# EPS_Stack_Header.net
KiCad netlist of a schematic drawn in Altium Designer
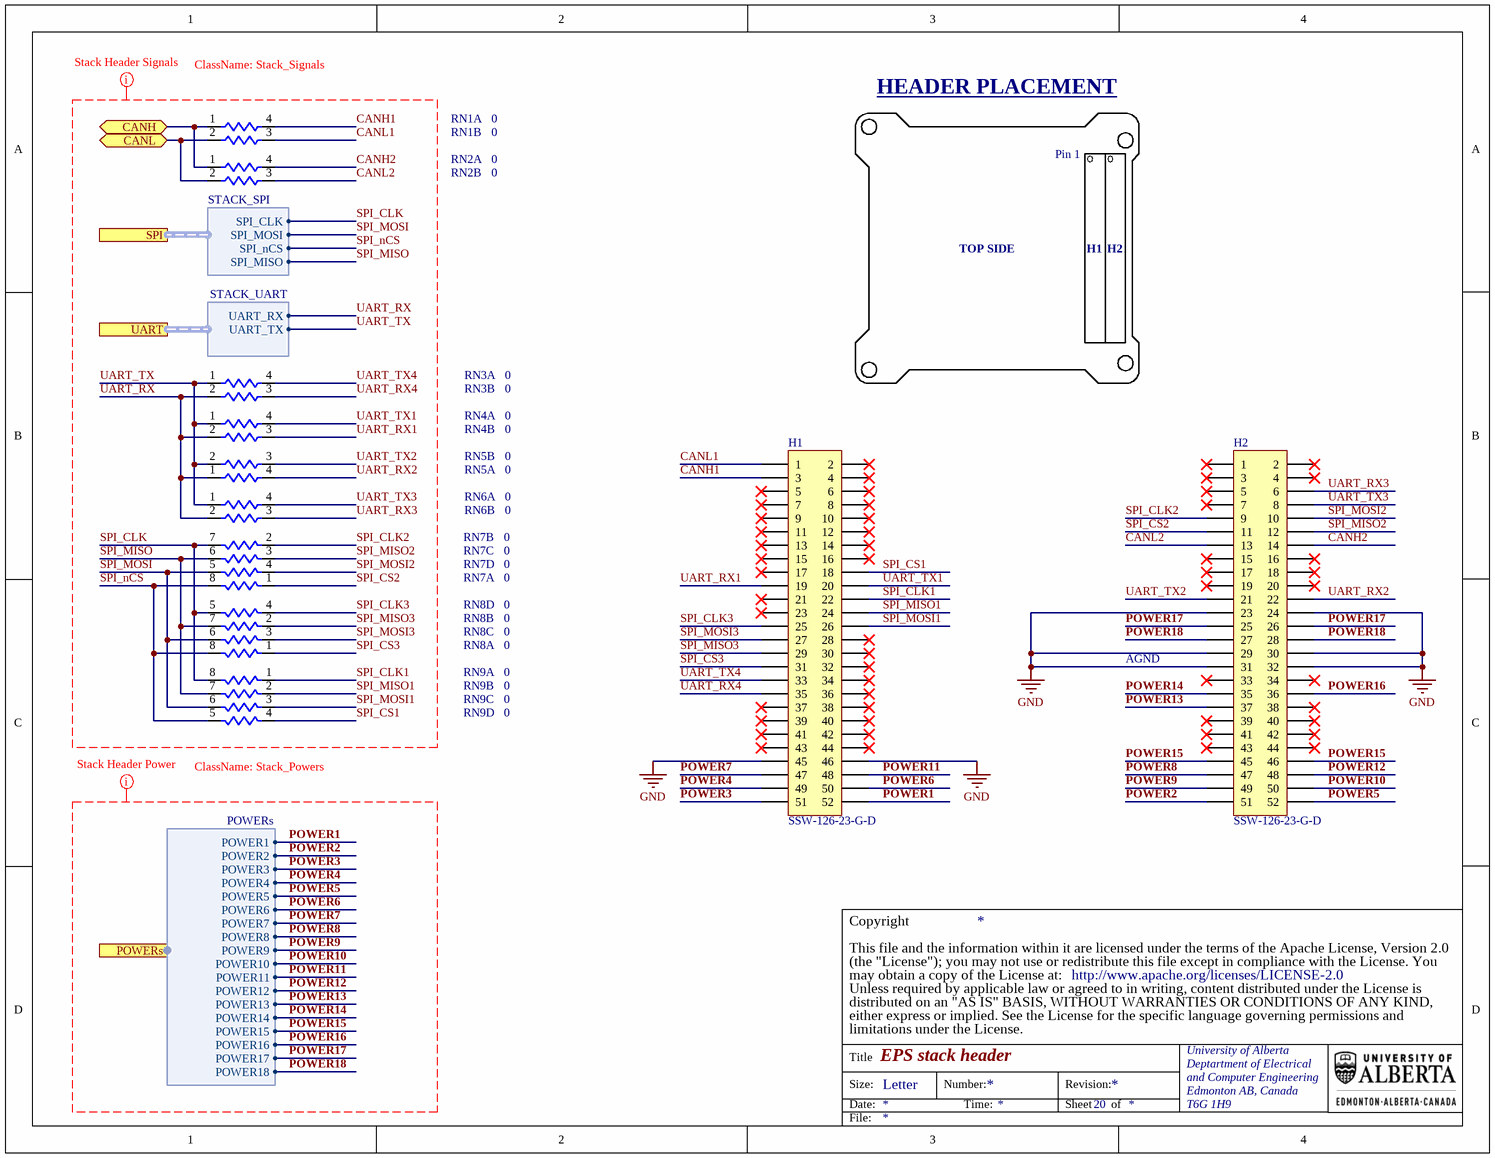
[diagram p0: EPS Stack Header.SchDoc]

(export (version "E")
  (design (tool "Eeschema 10.0.6"))
  (components
    (comp (ref "H1")
      (value "SSW-126-23-G-D")
      (footprint "SSW-126-23-G-D")
      (fields (field (name "PART NUMBER") "PP-SAM-00002") (field (name "PUBLISHER") "AlbertaSat"))
      (libsource (lib "Database") (part "Header 26X2"))
    )
    (comp (ref "H2")
      (value "SSW-126-23-G-D")
      (footprint "SSW-126-23-G-D")
      (fields (field (name "PART NUMBER") "PP-SAM-00002") (field (name "PUBLISHER") "AlbertaSat"))
      (libsource (lib "Database") (part "Header 26X2"))
    )
    (comp (ref "RN1")
      (value "0")
      (footprint "PANA-EXB24V")
      (description "RES ARRAY 2 RES ZERO OHM 0404")
      (fields (field (name "PART NUMBER") "20039") (field (name "MANUFACTURER PART NUMBER") "EXB-24VR000X"))
      (libsource (lib "Database") (part "Res2 Pack1"))
    )
    (comp (ref "RN2")
      (value "0")
      (footprint "PANA-EXB24V")
      (description "RES ARRAY 2 RES ZERO OHM 0404")
      (fields (field (name "PART NUMBER") "20039") (field (name "MANUFACTURER PART NUMBER") "EXB-24VR000X"))
      (libsource (lib "Database") (part "Res2 Pack1"))
    )
    (comp (ref "RN3")
      (value "0")
      (footprint "PANA-EXB24V")
      (description "RES ARRAY 2 RES ZERO OHM 0404")
      (fields (field (name "PART NUMBER") "20039") (field (name "MANUFACTURER PART NUMBER") "EXB-24VR000X"))
      (libsource (lib "Database") (part "Res2 Pack1"))
    )
    (comp (ref "RN4")
      (value "0")
      (footprint "PANA-EXB24V")
      (description "RES ARRAY 2 RES ZERO OHM 0404")
      (fields (field (name "PART NUMBER") "20039") (field (name "MANUFACTURER PART NUMBER") "EXB-24VR000X"))
      (libsource (lib "Database") (part "Res2 Pack1"))
    )
    (comp (ref "RN5")
      (value "0")
      (footprint "PANA-EXB24V")
      (description "RES ARRAY 2 RES ZERO OHM 0404")
      (fields (field (name "PART NUMBER") "20039") (field (name "MANUFACTURER PART NUMBER") "EXB-24VR000X"))
      (libsource (lib "Database") (part "Res2 Pack1"))
    )
    (comp (ref "RN6")
      (value "0")
      (footprint "PANA-EXB24V")
      (description "RES ARRAY 2 RES ZERO OHM 0404")
      (fields (field (name "PART NUMBER") "20039") (field (name "MANUFACTURER PART NUMBER") "EXB-24VR000X"))
      (libsource (lib "Database") (part "Res2 Pack1"))
    )
    (comp (ref "RN7")
      (value "0")
      (footprint "PANA-EXB28V")
      (description "RES ARRAY 4 RES ZERO OHM 0804")
      (fields (field (name "PART NUMBER") "19874") (field (name "MANUFACTURER PART NUMBER") "EXB-28VR000X"))
      (libsource (lib "Database") (part "Res4 Pack1"))
    )
    (comp (ref "RN8")
      (value "0")
      (footprint "PANA-EXB28V")
      (description "RES ARRAY 4 RES ZERO OHM 0804")
      (fields (field (name "PART NUMBER") "19874") (field (name "MANUFACTURER PART NUMBER") "EXB-28VR000X"))
      (libsource (lib "Database") (part "Res4 Pack1"))
    )
    (comp (ref "RN9")
      (value "0")
      (footprint "PANA-EXB28V")
      (description "RES ARRAY 4 RES ZERO OHM 0804")
      (fields (field (name "PART NUMBER") "19874") (field (name "MANUFACTURER PART NUMBER") "EXB-28VR000X"))
      (libsource (lib "Database") (part "Res4 Pack1"))
    )
  )
  (nets
    (net (code "4") (name "/CANH") (class "Default")
      (node (ref "RN1") (pin "1") (pinfunction "1_1") (pintype "passive"))
      (node (ref "RN2") (pin "1") (pinfunction "1_1") (pintype "passive"))
    )
    (net (code "5") (name "/CANH1") (class "Default")
      (node (ref "H1") (pin "3") (pinfunction "3_3") (pintype "passive"))
      (node (ref "RN1") (pin "4") (pinfunction "4_4") (pintype "passive"))
    )
    (net (code "6") (name "/CANH2") (class "Default")
      (node (ref "H2") (pin "14") (pinfunction "14_14") (pintype "passive"))
      (node (ref "RN2") (pin "4") (pinfunction "4_4") (pintype "passive"))
    )
    (net (code "7") (name "/CANL") (class "Default")
      (node (ref "RN1") (pin "2") (pinfunction "2_2") (pintype "passive"))
      (node (ref "RN2") (pin "2") (pinfunction "2_2") (pintype "passive"))
    )
    (net (code "8") (name "/CANL1") (class "Default")
      (node (ref "H1") (pin "1") (pinfunction "1_1") (pintype "passive"))
      (node (ref "RN1") (pin "3") (pinfunction "3_3") (pintype "passive"))
    )
    (net (code "9") (name "/CANL2") (class "Default")
      (node (ref "H2") (pin "13") (pinfunction "13_13") (pintype "passive"))
      (node (ref "RN2") (pin "3") (pinfunction "3_3") (pintype "passive"))
    )
    (net (code "10") (name "/POWER1") (class "Default")
      (node (ref "H1") (pin "52") (pinfunction "52_52") (pintype "passive"))
    )
    (net (code "11") (name "/POWER2") (class "Default")
      (node (ref "H2") (pin "51") (pinfunction "51_51") (pintype "passive"))
    )
    (net (code "12") (name "/POWER3") (class "Default")
      (node (ref "H1") (pin "51") (pinfunction "51_51") (pintype "passive"))
    )
    (net (code "13") (name "/POWER4") (class "Default")
      (node (ref "H1") (pin "49") (pinfunction "49_49") (pintype "passive"))
    )
    (net (code "14") (name "/POWER5") (class "Default")
      (node (ref "H2") (pin "52") (pinfunction "52_52") (pintype "passive"))
    )
    (net (code "15") (name "/POWER6") (class "Default")
      (node (ref "H1") (pin "50") (pinfunction "50_50") (pintype "passive"))
    )
    (net (code "16") (name "/POWER7") (class "Default")
      (node (ref "H1") (pin "47") (pinfunction "47_47") (pintype "passive"))
    )
    (net (code "17") (name "/POWER8") (class "Default")
      (node (ref "H2") (pin "47") (pinfunction "47_47") (pintype "passive"))
    )
    (net (code "18") (name "/POWER9") (class "Default")
      (node (ref "H2") (pin "49") (pinfunction "49_49") (pintype "passive"))
    )
    (net (code "19") (name "/POWER10") (class "Default")
      (node (ref "H2") (pin "50") (pinfunction "50_50") (pintype "passive"))
    )
    (net (code "20") (name "/POWER11") (class "Default")
      (node (ref "H1") (pin "48") (pinfunction "48_48") (pintype "passive"))
    )
    (net (code "21") (name "/POWER12") (class "Default")
      (node (ref "H2") (pin "48") (pinfunction "48_48") (pintype "passive"))
    )
    (net (code "22") (name "/POWER13") (class "Default")
      (node (ref "H2") (pin "37") (pinfunction "37_37") (pintype "passive"))
    )
    (net (code "23") (name "/POWER14") (class "Default")
      (node (ref "H2") (pin "35") (pinfunction "35_35") (pintype "passive"))
    )
    (net (code "24") (name "/POWER15") (class "Default")
      (node (ref "H2") (pin "45") (pinfunction "45_45") (pintype "passive"))
      (node (ref "H2") (pin "46") (pinfunction "46_46") (pintype "passive"))
    )
    (net (code "25") (name "/POWER16") (class "Default")
      (node (ref "H2") (pin "36") (pinfunction "36_36") (pintype "passive"))
    )
    (net (code "26") (name "/POWER17") (class "Default")
      (node (ref "H2") (pin "25") (pinfunction "25_25") (pintype "passive"))
      (node (ref "H2") (pin "26") (pinfunction "26_26") (pintype "passive"))
    )
    (net (code "27") (name "/POWER18") (class "Default")
      (node (ref "H2") (pin "27") (pinfunction "27_27") (pintype "passive"))
      (node (ref "H2") (pin "28") (pinfunction "28_28") (pintype "passive"))
    )
    (net (code "28") (name "/SPI_CLK") (class "Default")
      (node (ref "RN7") (pin "7") (pinfunction "7_7") (pintype "passive"))
      (node (ref "RN8") (pin "5") (pinfunction "5_5") (pintype "passive"))
      (node (ref "RN9") (pin "8") (pinfunction "8_8") (pintype "passive"))
    )
    (net (code "29") (name "/SPI_CLK1") (class "Default")
      (node (ref "H1") (pin "22") (pinfunction "22_22") (pintype "passive"))
      (node (ref "RN9") (pin "1") (pinfunction "1_1") (pintype "passive"))
    )
    (net (code "30") (name "/SPI_CLK2") (class "Default")
      (node (ref "H2") (pin "9") (pinfunction "9_9") (pintype "passive"))
      (node (ref "RN7") (pin "2") (pinfunction "2_2") (pintype "passive"))
    )
    (net (code "31") (name "/SPI_CLK3") (class "Default")
      (node (ref "H1") (pin "25") (pinfunction "25_25") (pintype "passive"))
      (node (ref "RN8") (pin "4") (pinfunction "4_4") (pintype "passive"))
    )
    (net (code "32") (name "/SPI_CS1") (class "Default")
      (node (ref "H1") (pin "18") (pinfunction "18_18") (pintype "passive"))
      (node (ref "RN9") (pin "4") (pinfunction "4_4") (pintype "passive"))
    )
    (net (code "33") (name "/SPI_CS2") (class "Default")
      (node (ref "H2") (pin "11") (pinfunction "11_11") (pintype "passive"))
      (node (ref "RN7") (pin "1") (pinfunction "1_1") (pintype "passive"))
    )
    (net (code "34") (name "/SPI_CS3") (class "Default")
      (node (ref "H1") (pin "31") (pinfunction "31_31") (pintype "passive"))
      (node (ref "RN8") (pin "1") (pinfunction "1_1") (pintype "passive"))
    )
    (net (code "35") (name "/SPI_MISO") (class "Default")
      (node (ref "RN7") (pin "6") (pinfunction "6_6") (pintype "passive"))
      (node (ref "RN8") (pin "7") (pinfunction "7_7") (pintype "passive"))
      (node (ref "RN9") (pin "7") (pinfunction "7_7") (pintype "passive"))
    )
    (net (code "36") (name "/SPI_MISO1") (class "Default")
      (node (ref "H1") (pin "24") (pinfunction "24_24") (pintype "passive"))
      (node (ref "RN9") (pin "2") (pinfunction "2_2") (pintype "passive"))
    )
    (net (code "37") (name "/SPI_MISO2") (class "Default")
      (node (ref "H2") (pin "12") (pinfunction "12_12") (pintype "passive"))
      (node (ref "RN7") (pin "3") (pinfunction "3_3") (pintype "passive"))
    )
    (net (code "38") (name "/SPI_MISO3") (class "Default")
      (node (ref "H1") (pin "29") (pinfunction "29_29") (pintype "passive"))
      (node (ref "RN8") (pin "2") (pinfunction "2_2") (pintype "passive"))
    )
    (net (code "39") (name "/SPI_MOSI") (class "Default")
      (node (ref "RN7") (pin "5") (pinfunction "5_5") (pintype "passive"))
      (node (ref "RN8") (pin "6") (pinfunction "6_6") (pintype "passive"))
      (node (ref "RN9") (pin "6") (pinfunction "6_6") (pintype "passive"))
    )
    (net (code "40") (name "/SPI_MOSI1") (class "Default")
      (node (ref "H1") (pin "26") (pinfunction "26_26") (pintype "passive"))
      (node (ref "RN9") (pin "3") (pinfunction "3_3") (pintype "passive"))
    )
    (net (code "41") (name "/SPI_MOSI2") (class "Default")
      (node (ref "H2") (pin "10") (pinfunction "10_10") (pintype "passive"))
      (node (ref "RN7") (pin "4") (pinfunction "4_4") (pintype "passive"))
    )
    (net (code "42") (name "/SPI_MOSI3") (class "Default")
      (node (ref "H1") (pin "27") (pinfunction "27_27") (pintype "passive"))
      (node (ref "RN8") (pin "3") (pinfunction "3_3") (pintype "passive"))
    )
    (net (code "43") (name "/SPI_nCS") (class "Default")
      (node (ref "RN7") (pin "8") (pinfunction "8_8") (pintype "passive"))
      (node (ref "RN8") (pin "8") (pinfunction "8_8") (pintype "passive"))
      (node (ref "RN9") (pin "5") (pinfunction "5_5") (pintype "passive"))
    )
    (net (code "44") (name "/UART_RX") (class "Default")
      (node (ref "RN3") (pin "2") (pinfunction "2_2") (pintype "passive"))
      (node (ref "RN4") (pin "2") (pinfunction "2_2") (pintype "passive"))
      (node (ref "RN5") (pin "1") (pinfunction "1_1") (pintype "passive"))
      (node (ref "RN6") (pin "2") (pinfunction "2_2") (pintype "passive"))
    )
    (net (code "45") (name "/UART_RX1") (class "Default")
      (node (ref "H1") (pin "19") (pinfunction "19_19") (pintype "passive"))
      (node (ref "RN4") (pin "3") (pinfunction "3_3") (pintype "passive"))
    )
    (net (code "46") (name "/UART_RX2") (class "Default")
      (node (ref "H2") (pin "22") (pinfunction "22_22") (pintype "passive"))
      (node (ref "RN5") (pin "4") (pinfunction "4_4") (pintype "passive"))
    )
    (net (code "47") (name "/UART_RX3") (class "Default")
      (node (ref "H2") (pin "6") (pinfunction "6_6") (pintype "passive"))
      (node (ref "RN6") (pin "3") (pinfunction "3_3") (pintype "passive"))
    )
    (net (code "48") (name "/UART_RX4") (class "Default")
      (node (ref "H1") (pin "35") (pinfunction "35_35") (pintype "passive"))
      (node (ref "RN3") (pin "3") (pinfunction "3_3") (pintype "passive"))
    )
    (net (code "49") (name "/UART_TX") (class "Default")
      (node (ref "RN3") (pin "1") (pinfunction "1_1") (pintype "passive"))
      (node (ref "RN4") (pin "1") (pinfunction "1_1") (pintype "passive"))
      (node (ref "RN5") (pin "2") (pinfunction "2_2") (pintype "passive"))
      (node (ref "RN6") (pin "1") (pinfunction "1_1") (pintype "passive"))
    )
    (net (code "50") (name "/UART_TX1") (class "Default")
      (node (ref "H1") (pin "20") (pinfunction "20_20") (pintype "passive"))
      (node (ref "RN4") (pin "4") (pinfunction "4_4") (pintype "passive"))
    )
    (net (code "51") (name "/UART_TX2") (class "Default")
      (node (ref "H2") (pin "21") (pinfunction "21_21") (pintype "passive"))
      (node (ref "RN5") (pin "3") (pinfunction "3_3") (pintype "passive"))
    )
    (net (code "52") (name "/UART_TX3") (class "Default")
      (node (ref "H2") (pin "8") (pinfunction "8_8") (pintype "passive"))
      (node (ref "RN6") (pin "4") (pinfunction "4_4") (pintype "passive"))
    )
    (net (code "53") (name "/UART_TX4") (class "Default")
      (node (ref "H1") (pin "33") (pinfunction "33_33") (pintype "passive"))
      (node (ref "RN3") (pin "4") (pinfunction "4_4") (pintype "passive"))
    )
    (net (code "57") (name "GND") (class "Default")
      (node (ref "H1") (pin "45") (pinfunction "45_45") (pintype "passive"))
      (node (ref "H1") (pin "46") (pinfunction "46_46") (pintype "passive"))
      (node (ref "H2") (pin "23") (pinfunction "23_23") (pintype "passive"))
      (node (ref "H2") (pin "24") (pinfunction "24_24") (pintype "passive"))
      (node (ref "H2") (pin "29") (pinfunction "29_29") (pintype "passive"))
      (node (ref "H2") (pin "30") (pinfunction "30_30") (pintype "passive"))
      (node (ref "H2") (pin "31") (pinfunction "31_31") (pintype "passive"))
      (node (ref "H2") (pin "32") (pinfunction "32_32") (pintype "passive"))
    )
    (net (code "58") (name "unconnected-(H1-Pad2)") (class "Default")
      (node (ref "H1") (pin "2") (pinfunction "2_2") (pintype "passive+no_connect"))
    )
    (net (code "59") (name "unconnected-(H1-Pad4)") (class "Default")
      (node (ref "H1") (pin "4") (pinfunction "4_4") (pintype "passive+no_connect"))
    )
    (net (code "60") (name "unconnected-(H1-Pad5)") (class "Default")
      (node (ref "H1") (pin "5") (pinfunction "5_5") (pintype "passive+no_connect"))
    )
    (net (code "61") (name "unconnected-(H1-Pad6)") (class "Default")
      (node (ref "H1") (pin "6") (pinfunction "6_6") (pintype "passive+no_connect"))
    )
    (net (code "62") (name "unconnected-(H1-Pad7)") (class "Default")
      (node (ref "H1") (pin "7") (pinfunction "7_7") (pintype "passive+no_connect"))
    )
    (net (code "63") (name "unconnected-(H1-Pad8)") (class "Default")
      (node (ref "H1") (pin "8") (pinfunction "8_8") (pintype "passive+no_connect"))
    )
    (net (code "64") (name "unconnected-(H1-Pad9)") (class "Default")
      (node (ref "H1") (pin "9") (pinfunction "9_9") (pintype "passive+no_connect"))
    )
    (net (code "65") (name "unconnected-(H1-Pad10)") (class "Default")
      (node (ref "H1") (pin "10") (pinfunction "10_10") (pintype "passive+no_connect"))
    )
    (net (code "66") (name "unconnected-(H1-Pad11)") (class "Default")
      (node (ref "H1") (pin "11") (pinfunction "11_11") (pintype "passive+no_connect"))
    )
    (net (code "67") (name "unconnected-(H1-Pad12)") (class "Default")
      (node (ref "H1") (pin "12") (pinfunction "12_12") (pintype "passive+no_connect"))
    )
    (net (code "68") (name "unconnected-(H1-Pad13)") (class "Default")
      (node (ref "H1") (pin "13") (pinfunction "13_13") (pintype "passive+no_connect"))
    )
    (net (code "69") (name "unconnected-(H1-Pad14)") (class "Default")
      (node (ref "H1") (pin "14") (pinfunction "14_14") (pintype "passive+no_connect"))
    )
    (net (code "70") (name "unconnected-(H1-Pad15)") (class "Default")
      (node (ref "H1") (pin "15") (pinfunction "15_15") (pintype "passive+no_connect"))
    )
    (net (code "71") (name "unconnected-(H1-Pad16)") (class "Default")
      (node (ref "H1") (pin "16") (pinfunction "16_16") (pintype "passive+no_connect"))
    )
    (net (code "72") (name "unconnected-(H1-Pad17)") (class "Default")
      (node (ref "H1") (pin "17") (pinfunction "17_17") (pintype "passive+no_connect"))
    )
    (net (code "73") (name "unconnected-(H1-Pad21)") (class "Default")
      (node (ref "H1") (pin "21") (pinfunction "21_21") (pintype "passive+no_connect"))
    )
    (net (code "74") (name "unconnected-(H1-Pad23)") (class "Default")
      (node (ref "H1") (pin "23") (pinfunction "23_23") (pintype "passive+no_connect"))
    )
    (net (code "75") (name "unconnected-(H1-Pad28)") (class "Default")
      (node (ref "H1") (pin "28") (pinfunction "28_28") (pintype "passive+no_connect"))
    )
    (net (code "76") (name "unconnected-(H1-Pad30)") (class "Default")
      (node (ref "H1") (pin "30") (pinfunction "30_30") (pintype "passive+no_connect"))
    )
    (net (code "77") (name "unconnected-(H1-Pad32)") (class "Default")
      (node (ref "H1") (pin "32") (pinfunction "32_32") (pintype "passive+no_connect"))
    )
    (net (code "78") (name "unconnected-(H1-Pad34)") (class "Default")
      (node (ref "H1") (pin "34") (pinfunction "34_34") (pintype "passive+no_connect"))
    )
    (net (code "79") (name "unconnected-(H1-Pad36)") (class "Default")
      (node (ref "H1") (pin "36") (pinfunction "36_36") (pintype "passive+no_connect"))
    )
    (net (code "80") (name "unconnected-(H1-Pad37)") (class "Default")
      (node (ref "H1") (pin "37") (pinfunction "37_37") (pintype "passive+no_connect"))
    )
    (net (code "81") (name "unconnected-(H1-Pad38)") (class "Default")
      (node (ref "H1") (pin "38") (pinfunction "38_38") (pintype "passive+no_connect"))
    )
    (net (code "82") (name "unconnected-(H1-Pad39)") (class "Default")
      (node (ref "H1") (pin "39") (pinfunction "39_39") (pintype "passive+no_connect"))
    )
    (net (code "83") (name "unconnected-(H1-Pad40)") (class "Default")
      (node (ref "H1") (pin "40") (pinfunction "40_40") (pintype "passive+no_connect"))
    )
    (net (code "84") (name "unconnected-(H1-Pad41)") (class "Default")
      (node (ref "H1") (pin "41") (pinfunction "41_41") (pintype "passive+no_connect"))
    )
    (net (code "85") (name "unconnected-(H1-Pad42)") (class "Default")
      (node (ref "H1") (pin "42") (pinfunction "42_42") (pintype "passive+no_connect"))
    )
    (net (code "86") (name "unconnected-(H1-Pad43)") (class "Default")
      (node (ref "H1") (pin "43") (pinfunction "43_43") (pintype "passive+no_connect"))
    )
    (net (code "87") (name "unconnected-(H1-Pad44)") (class "Default")
      (node (ref "H1") (pin "44") (pinfunction "44_44") (pintype "passive+no_connect"))
    )
    (net (code "88") (name "unconnected-(H2-Pad1)") (class "Default")
      (node (ref "H2") (pin "1") (pinfunction "1_1") (pintype "passive+no_connect"))
    )
    (net (code "89") (name "unconnected-(H2-Pad2)") (class "Default")
      (node (ref "H2") (pin "2") (pinfunction "2_2") (pintype "passive+no_connect"))
    )
    (net (code "90") (name "unconnected-(H2-Pad3)") (class "Default")
      (node (ref "H2") (pin "3") (pinfunction "3_3") (pintype "passive+no_connect"))
    )
    (net (code "91") (name "unconnected-(H2-Pad4)") (class "Default")
      (node (ref "H2") (pin "4") (pinfunction "4_4") (pintype "passive+no_connect"))
    )
    (net (code "92") (name "unconnected-(H2-Pad5)") (class "Default")
      (node (ref "H2") (pin "5") (pinfunction "5_5") (pintype "passive+no_connect"))
    )
    (net (code "93") (name "unconnected-(H2-Pad7)") (class "Default")
      (node (ref "H2") (pin "7") (pinfunction "7_7") (pintype "passive+no_connect"))
    )
    (net (code "94") (name "unconnected-(H2-Pad15)") (class "Default")
      (node (ref "H2") (pin "15") (pinfunction "15_15") (pintype "passive+no_connect"))
    )
    (net (code "95") (name "unconnected-(H2-Pad16)") (class "Default")
      (node (ref "H2") (pin "16") (pinfunction "16_16") (pintype "passive+no_connect"))
    )
    (net (code "96") (name "unconnected-(H2-Pad17)") (class "Default")
      (node (ref "H2") (pin "17") (pinfunction "17_17") (pintype "passive+no_connect"))
    )
    (net (code "97") (name "unconnected-(H2-Pad18)") (class "Default")
      (node (ref "H2") (pin "18") (pinfunction "18_18") (pintype "passive+no_connect"))
    )
    (net (code "98") (name "unconnected-(H2-Pad19)") (class "Default")
      (node (ref "H2") (pin "19") (pinfunction "19_19") (pintype "passive+no_connect"))
    )
    (net (code "99") (name "unconnected-(H2-Pad20)") (class "Default")
      (node (ref "H2") (pin "20") (pinfunction "20_20") (pintype "passive+no_connect"))
    )
    (net (code "100") (name "unconnected-(H2-Pad33)") (class "Default")
      (node (ref "H2") (pin "33") (pinfunction "33_33") (pintype "passive+no_connect"))
    )
    (net (code "101") (name "unconnected-(H2-Pad34)") (class "Default")
      (node (ref "H2") (pin "34") (pinfunction "34_34") (pintype "passive+no_connect"))
    )
    (net (code "102") (name "unconnected-(H2-Pad38)") (class "Default")
      (node (ref "H2") (pin "38") (pinfunction "38_38") (pintype "passive+no_connect"))
    )
    (net (code "103") (name "unconnected-(H2-Pad39)") (class "Default")
      (node (ref "H2") (pin "39") (pinfunction "39_39") (pintype "passive+no_connect"))
    )
    (net (code "104") (name "unconnected-(H2-Pad40)") (class "Default")
      (node (ref "H2") (pin "40") (pinfunction "40_40") (pintype "passive+no_connect"))
    )
    (net (code "105") (name "unconnected-(H2-Pad41)") (class "Default")
      (node (ref "H2") (pin "41") (pinfunction "41_41") (pintype "passive+no_connect"))
    )
    (net (code "106") (name "unconnected-(H2-Pad42)") (class "Default")
      (node (ref "H2") (pin "42") (pinfunction "42_42") (pintype "passive+no_connect"))
    )
    (net (code "107") (name "unconnected-(H2-Pad43)") (class "Default")
      (node (ref "H2") (pin "43") (pinfunction "43_43") (pintype "passive+no_connect"))
    )
    (net (code "108") (name "unconnected-(H2-Pad44)") (class "Default")
      (node (ref "H2") (pin "44") (pinfunction "44_44") (pintype "passive+no_connect"))
    )
  )
)
